# aku_tolto.net
KiCad netlist of a schematic drawn in EAGLE
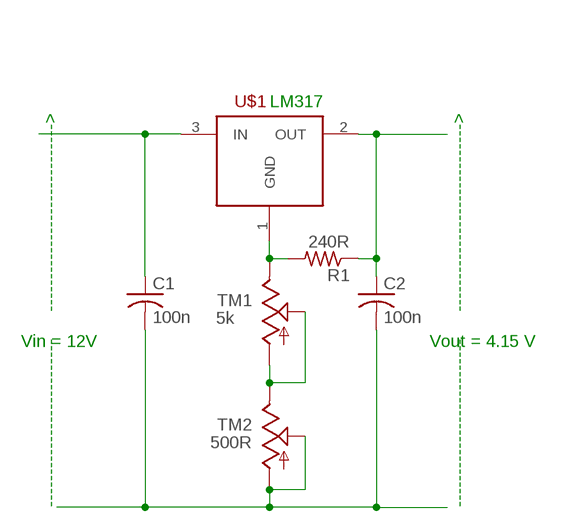
[diagram p0: schematic, sheet 1]

(export (version "E")
  (design (tool "Eeschema 10.0.6"))
  (components
    (comp (ref "C1")
      (value "100n")
      (footprint "eagle-import:C025_050-035X075")
      (libsource (lib "eagle-import") (part "C-US025_050-035X075"))
    )
    (comp (ref "C2")
      (value "100n")
      (footprint "eagle-import:C025_050-035X075")
      (libsource (lib "eagle-import") (part "C-US025_050-035X075"))
    )
    (comp (ref "R1")
      (value "240R")
      (footprint "eagle-import:0204V")
      (libsource (lib "eagle-import") (part "R-US_0204/2V"))
    )
    (comp (ref "TM1")
      (value "5k")
      (footprint "eagle-import:6MM")
      (libsource (lib "eagle-import") (part "TRIM"))
    )
    (comp (ref "TM2")
      (value "500R")
      (footprint "eagle-import:6MM")
      (libsource (lib "eagle-import") (part "TRIM"))
    )
    (comp (ref "U$1")
      (value "LM317")
      (footprint "eagle-import:TO-220")
      (libsource (lib "eagle-import") (part "LM317"))
    )
  )
  (nets
    (net (code "1") (name "Net-(C1-Pad2)") (class "Default")
      (node (ref "C1") (pin "2") (pinfunction "2_2") (pintype "passive"))
      (node (ref "C2") (pin "2") (pinfunction "2_2") (pintype "passive"))
      (node (ref "TM2") (pin "A") (pinfunction "A_A") (pintype "passive"))
      (node (ref "TM2") (pin "S") (pinfunction "S_S") (pintype "passive"))
    )
    (net (code "2") (name "Net-(TM1-PadA)") (class "Default")
      (node (ref "TM1") (pin "A") (pinfunction "A_A") (pintype "passive"))
      (node (ref "TM1") (pin "S") (pinfunction "S_S") (pintype "passive"))
      (node (ref "TM2") (pin "E") (pinfunction "E_E") (pintype "passive"))
    )
    (net (code "3") (name "Net-(U$1-GND)") (class "Default")
      (node (ref "R1") (pin "2") (pinfunction "2_2") (pintype "passive"))
      (node (ref "TM1") (pin "E") (pinfunction "E_E") (pintype "passive"))
      (node (ref "U$1") (pin "1") (pinfunction "GND_1") (pintype "bidirectional"))
    )
    (net (code "4") (name "Net-(U$1-IN)") (class "Default")
      (node (ref "C1") (pin "1") (pinfunction "1_1") (pintype "passive"))
      (node (ref "U$1") (pin "3") (pinfunction "IN_3") (pintype "bidirectional"))
    )
    (net (code "5") (name "Net-(U$1-OUT)") (class "Default")
      (node (ref "C2") (pin "1") (pinfunction "1_1") (pintype "passive"))
      (node (ref "R1") (pin "1") (pinfunction "1_1") (pintype "passive"))
      (node (ref "U$1") (pin "2") (pinfunction "OUT_2") (pintype "bidirectional"))
    )
  )
)
